# Yitran_IT900_Hutschiene_PIM7A_1_3.net
KiCad netlist of a schematic drawn in EAGLE
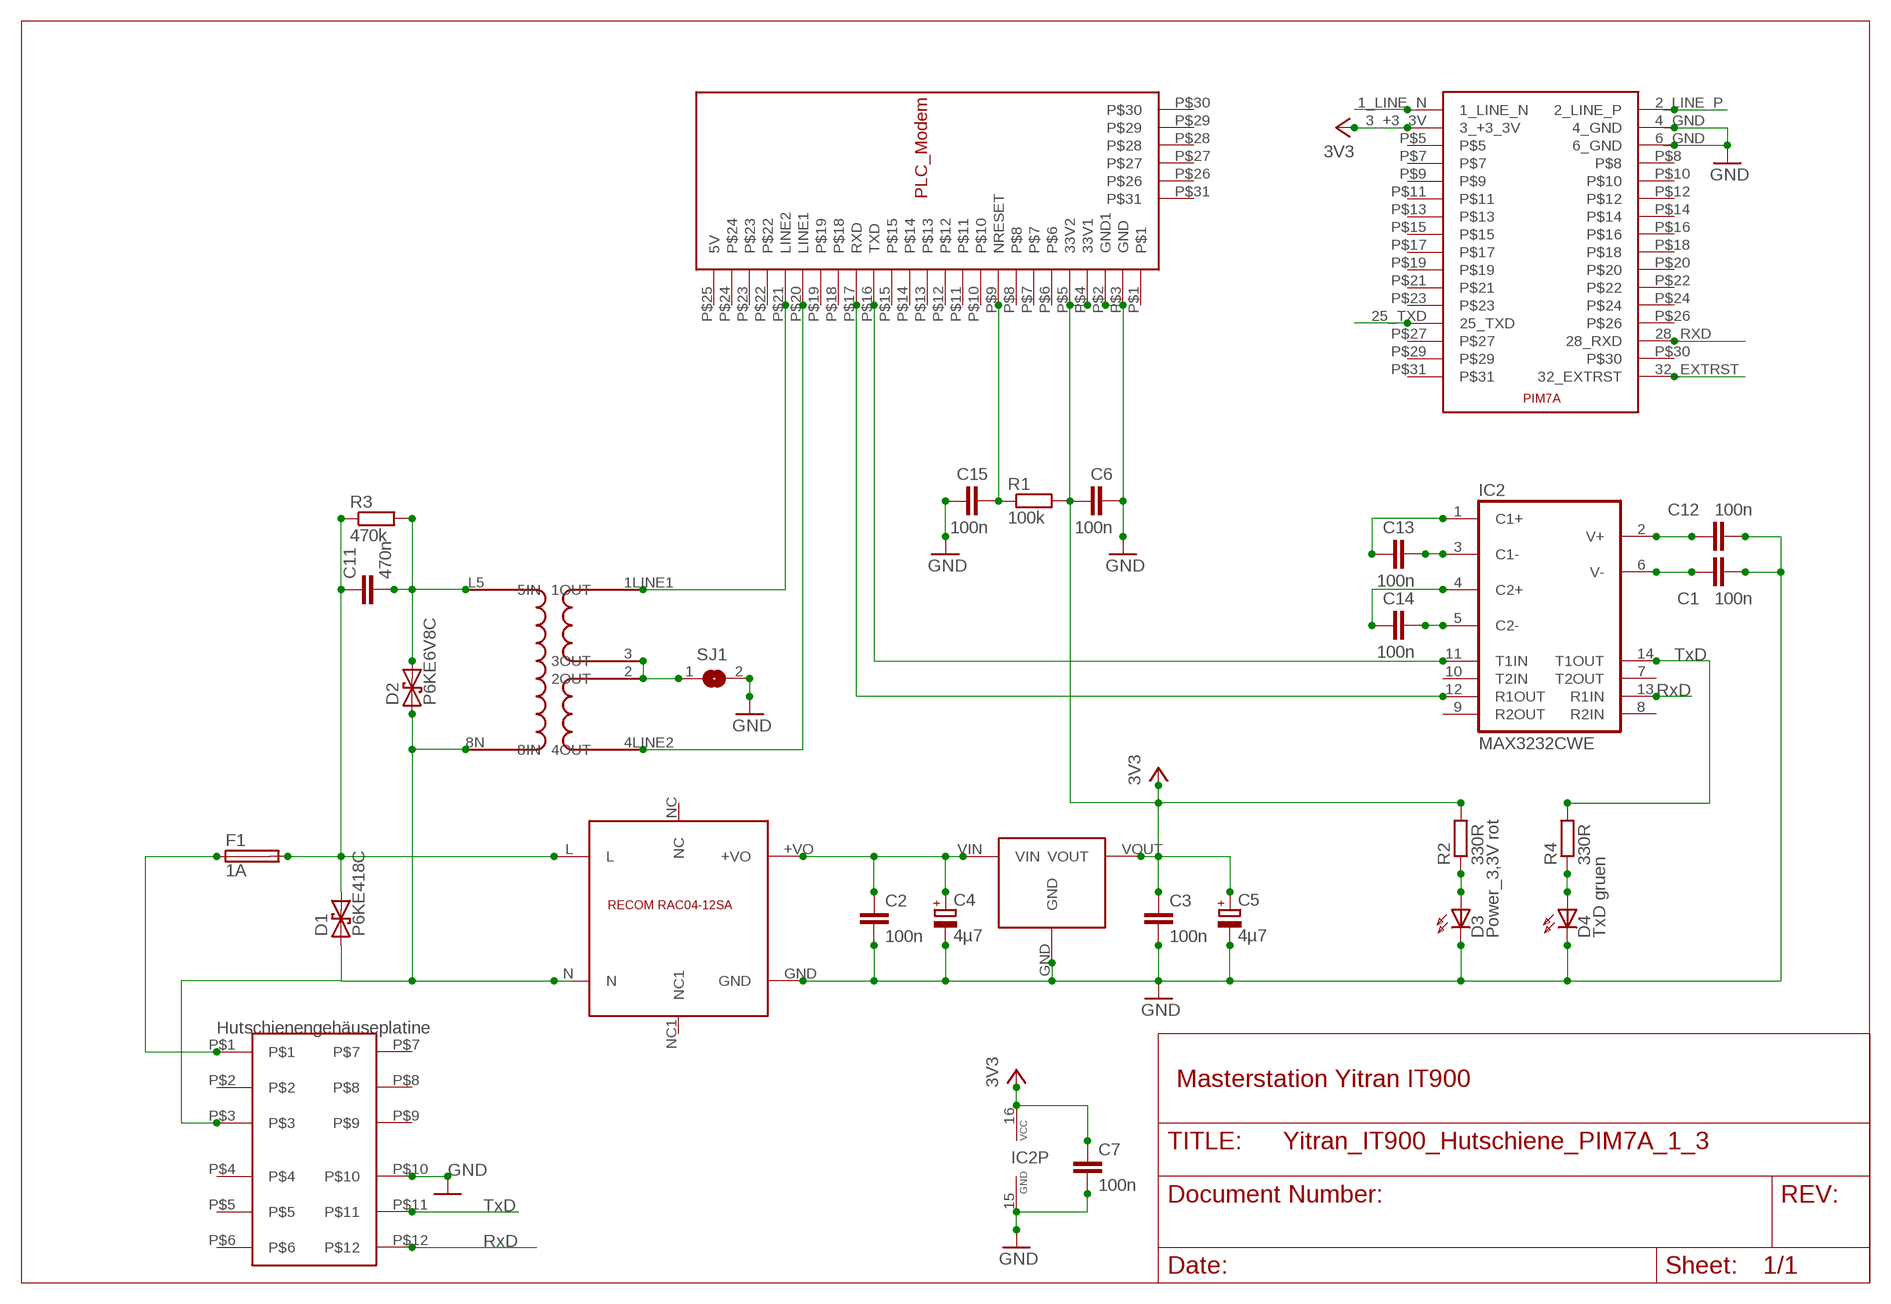
[diagram p0: schematic, sheet 1]

(export (version "E")
  (design (tool "Eeschema 10.0.6"))
  (components
    (comp (ref "C1")
      (value "100n")
      (footprint "eagle-import:C1206K")
      (libsource (lib "eagle-import") (part "C-EUC1206K"))
    )
    (comp (ref "C2")
      (value "100n")
      (footprint "eagle-import:C1206K")
      (libsource (lib "eagle-import") (part "C-EUC1206K"))
    )
    (comp (ref "C3")
      (value "100n")
      (footprint "eagle-import:C1206K")
      (libsource (lib "eagle-import") (part "C-EUC1206K"))
    )
    (comp (ref "C4")
      (value "4µ7")
      (footprint "eagle-import:E2,5-5")
      (libsource (lib "eagle-import") (part "CPOL-EUE2.5-5"))
    )
    (comp (ref "C5")
      (value "4µ7")
      (footprint "eagle-import:E2,5-5")
      (libsource (lib "eagle-import") (part "CPOL-EUE2.5-5"))
    )
    (comp (ref "C6")
      (value "100n")
      (footprint "eagle-import:C1206K")
      (libsource (lib "eagle-import") (part "C-EUC1206K"))
    )
    (comp (ref "C7")
      (value "100n")
      (footprint "eagle-import:C1206K")
      (libsource (lib "eagle-import") (part "C-EUC1206K"))
    )
    (comp (ref "C11")
      (value "470n")
      (footprint "eagle-import:C150-091X182")
      (libsource (lib "eagle-import") (part "C-EU150-091X182"))
    )
    (comp (ref "C12")
      (value "100n")
      (footprint "eagle-import:C1206K")
      (libsource (lib "eagle-import") (part "C-EUC1206K"))
    )
    (comp (ref "C13")
      (value "100n")
      (footprint "eagle-import:C1206K")
      (libsource (lib "eagle-import") (part "C-EUC1206K"))
    )
    (comp (ref "C14")
      (value "100n")
      (footprint "eagle-import:C1206K")
      (libsource (lib "eagle-import") (part "C-EUC1206K"))
    )
    (comp (ref "C15")
      (value "100n")
      (footprint "eagle-import:C1206K")
      (libsource (lib "eagle-import") (part "C-EUC1206K"))
    )
    (comp (ref "D1")
      (value "P6KE418C")
      (footprint "eagle-import:CB417-15")
      (libsource (lib "eagle-import") (part "P6KEXXC"))
    )
    (comp (ref "D2")
      (value "P6KE6V8C")
      (footprint "eagle-import:CB417-15")
      (libsource (lib "eagle-import") (part "P6KEXXC"))
    )
    (comp (ref "D3")
      (value "Power_3,3V rot")
      (footprint "eagle-import:HLMP6")
      (fields (field (name "MF") "AGILENT TECHNOLOGIES") (field (name "MPN") "HLMP-6500"))
      (libsource (lib "eagle-import") (part "HLMP6"))
    )
    (comp (ref "D4")
      (value "TxD gruen")
      (footprint "eagle-import:HLMP6")
      (fields (field (name "MF") "AGILENT TECHNOLOGIES") (field (name "MPN") "HLMP-6500"))
      (libsource (lib "eagle-import") (part "HLMP6"))
    )
    (comp (ref "F1")
      (value "1A")
      (footprint "eagle-import:TR5")
      (libsource (lib "eagle-import") (part "TR5"))
    )
    (comp (ref "IC2")
      (value "MAX3232CWE")
      (footprint "eagle-import:SO16L")
      (fields (field (name "MF") "MAXIM") (field (name "MPN") "MAX3232CWE+"))
      (libsource (lib "eagle-import") (part "MAX3232WEC"))
    )
    (comp (ref "R1")
      (value "100k")
      (footprint "eagle-import:M1406")
      (libsource (lib "eagle-import") (part "R-EU_M1406"))
    )
    (comp (ref "R2")
      (value "330R")
      (footprint "eagle-import:R1206")
      (libsource (lib "eagle-import") (part "R-EU_R1206"))
    )
    (comp (ref "R3")
      (value "470k")
      (footprint "eagle-import:0309_10")
      (libsource (lib "eagle-import") (part "R-EU_0309/10"))
    )
    (comp (ref "R4")
      (value "330R")
      (footprint "eagle-import:R1206")
      (libsource (lib "eagle-import") (part "R-EU_R1206"))
    )
    (comp (ref "SJ1")
      (value "SJW")
      (footprint "eagle-import:SJW")
      (libsource (lib "eagle-import") (part "SJW"))
    )
    (comp (ref "U$1")
      (value "RECOM_783_3")
      (footprint "eagle-import:RECOM785X")
      (libsource (lib "eagle-import") (part "RECOM_785_05"))
    )
    (comp (ref "U$2")
      (value "LDG-A-12")
      (footprint "eagle-import:LDG-A-12")
      (libsource (lib "eagle-import") (part "LDG-A-12"))
    )
    (comp (ref "U$3")
      (value "MODEMSTECKER")
      (footprint "eagle-import:MODEM_FUSS")
      (libsource (lib "eagle-import") (part "MODEMSTECKER"))
    )
    (comp (ref "U$4")
      (value "IT900PIM7A")
      (footprint "eagle-import:IT900PIM7A")
      (libsource (lib "eagle-import") (part "IT900PIM7A"))
    )
    (comp (ref "U$9")
      (value "RECOM_RAC04_12SA")
      (footprint "eagle-import:RAC04_12SA")
      (libsource (lib "eagle-import") (part "RECOM_RAC04_12SA"))
    )
    (comp (ref "U$10")
      (value "PLC_UEBERTRAGER_V2")
      (footprint "eagle-import:PLC-UEBERTRAGER_V2")
      (libsource (lib "eagle-import") (part "PLC_UEBERTRAGER_V2"))
    )
  )
  (nets
    (net (code "1") (name "/EXTRST") (class "Default")
      (node (ref "C15") (pin "2") (pinfunction "2_2") (pintype "passive"))
      (node (ref "R1") (pin "1") (pinfunction "1_1") (pintype "passive"))
      (node (ref "U$3") (pin "P$9") (pinfunction "NRESET_P$9") (pintype "bidirectional"))
      (node (ref "U$4") (pin "32_EXTRST") (pinfunction "32_EXTRST_32_EXTRST") (pintype "bidirectional"))
    )
    (net (code "2") (name "/LINE1") (class "Default")
      (node (ref "U$10") (pin "4LINE2") (pinfunction "4OUT_4LINE2") (pintype "output"))
      (node (ref "U$3") (pin "P$20") (pinfunction "LINE1_P$20") (pintype "bidirectional"))
      (node (ref "U$4") (pin "1_LINE_N") (pinfunction "1_LINE_N_1_LINE_N") (pintype "bidirectional"))
    )
    (net (code "3") (name "/LINE2") (class "Default")
      (node (ref "U$10") (pin "1LINE1") (pinfunction "1OUT_1LINE1") (pintype "output"))
      (node (ref "U$3") (pin "P$21") (pinfunction "LINE2_P$21") (pintype "bidirectional"))
      (node (ref "U$4") (pin "2_LINE_P") (pinfunction "2_LINE_P_2_LINE_P") (pintype "bidirectional"))
    )
    (net (code "4") (name "/RX") (class "Default")
      (node (ref "IC2") (pin "12") (pinfunction "R1OUT_12") (pintype "output"))
      (node (ref "U$3") (pin "P$17") (pinfunction "RXD_P$17") (pintype "bidirectional"))
      (node (ref "U$4") (pin "28_RXD") (pinfunction "28_RXD_28_RXD") (pintype "bidirectional"))
    )
    (net (code "5") (name "/RXD") (class "Default")
      (node (ref "IC2") (pin "13") (pinfunction "R1IN_13") (pintype "input"))
      (node (ref "U$2") (pin "P$12") (pinfunction "P$12_P$12") (pintype "bidirectional"))
    )
    (net (code "6") (name "/TX") (class "Default")
      (node (ref "IC2") (pin "11") (pinfunction "T1IN_11") (pintype "input"))
      (node (ref "U$3") (pin "P$16") (pinfunction "TXD_P$16") (pintype "bidirectional"))
      (node (ref "U$4") (pin "25_TXD") (pinfunction "25_TXD_25_TXD") (pintype "bidirectional"))
    )
    (net (code "7") (name "/TXD") (class "Default")
      (node (ref "IC2") (pin "14") (pinfunction "T1OUT_14") (pintype "output"))
      (node (ref "R4") (pin "2") (pinfunction "2_2") (pintype "passive"))
      (node (ref "U$2") (pin "P$11") (pinfunction "P$11_P$11") (pintype "bidirectional"))
    )
    (net (code "8") (name "3V3") (class "Default")
      (node (ref "C3") (pin "1") (pinfunction "1_1") (pintype "passive"))
      (node (ref "C5") (pin "+") (pinfunction "+_+") (pintype "passive"))
      (node (ref "C6") (pin "1") (pinfunction "1_1") (pintype "passive"))
      (node (ref "C7") (pin "1") (pinfunction "1_1") (pintype "passive"))
      (node (ref "IC2") (pin "16") (pinfunction "VCC_16") (pintype "power_in"))
      (node (ref "R1") (pin "2") (pinfunction "2_2") (pintype "passive"))
      (node (ref "R2") (pin "2") (pinfunction "2_2") (pintype "passive"))
      (node (ref "U$1") (pin "VOUT") (pinfunction "VOUT_VOUT") (pintype "bidirectional"))
      (node (ref "U$3") (pin "P$4") (pinfunction "33V1_P$4") (pintype "bidirectional"))
      (node (ref "U$3") (pin "P$5") (pinfunction "33V2_P$5") (pintype "bidirectional"))
      (node (ref "U$4") (pin "3_+3_3V") (pinfunction "3_+3_3V_3_+3_3V") (pintype "bidirectional"))
    )
    (net (code "9") (name "GND") (class "Default")
      (node (ref "C1") (pin "2") (pinfunction "2_2") (pintype "passive"))
      (node (ref "C12") (pin "2") (pinfunction "2_2") (pintype "passive"))
      (node (ref "C15") (pin "1") (pinfunction "1_1") (pintype "passive"))
      (node (ref "C2") (pin "2") (pinfunction "2_2") (pintype "passive"))
      (node (ref "C3") (pin "2") (pinfunction "2_2") (pintype "passive"))
      (node (ref "C4") (pin "-") (pinfunction "-_-") (pintype "passive"))
      (node (ref "C5") (pin "-") (pinfunction "-_-") (pintype "passive"))
      (node (ref "C6") (pin "2") (pinfunction "2_2") (pintype "passive"))
      (node (ref "C7") (pin "2") (pinfunction "2_2") (pintype "passive"))
      (node (ref "D3") (pin "K") (pinfunction "K_K") (pintype "passive"))
      (node (ref "D4") (pin "K") (pinfunction "K_K") (pintype "passive"))
      (node (ref "IC2") (pin "15") (pinfunction "GND_15") (pintype "power_in"))
      (node (ref "SJ1") (pin "2") (pinfunction "2_2") (pintype "passive"))
      (node (ref "U$1") (pin "GND") (pinfunction "GND_GND") (pintype "bidirectional"))
      (node (ref "U$2") (pin "P$10") (pinfunction "P$10_P$10") (pintype "bidirectional"))
      (node (ref "U$3") (pin "P$2") (pinfunction "GND1_P$2") (pintype "bidirectional"))
      (node (ref "U$3") (pin "P$3") (pinfunction "GND_P$3") (pintype "bidirectional"))
      (node (ref "U$4") (pin "4_GND") (pinfunction "4_GND_4_GND") (pintype "bidirectional"))
      (node (ref "U$4") (pin "6_GND") (pinfunction "6_GND_6_GND") (pintype "bidirectional"))
      (node (ref "U$9") (pin "GND") (pinfunction "GND_GND") (pintype "bidirectional"))
    )
    (net (code "10") (name "Net-(C2-Pad1)") (class "Default")
      (node (ref "C2") (pin "1") (pinfunction "1_1") (pintype "passive"))
      (node (ref "C4") (pin "+") (pinfunction "+_+") (pintype "passive"))
      (node (ref "U$1") (pin "VIN") (pinfunction "VIN_VIN") (pintype "bidirectional"))
      (node (ref "U$9") (pin "+VO") (pinfunction "+VO_+VO") (pintype "bidirectional"))
    )
    (net (code "11") (name "Net-(D1-1)") (class "Default")
      (node (ref "D1") (pin "A") (pinfunction "1_A") (pintype "passive"))
      (node (ref "D2") (pin "A") (pinfunction "1_A") (pintype "passive"))
      (node (ref "U$10") (pin "8N") (pinfunction "8IN_8N") (pintype "input"))
      (node (ref "U$2") (pin "P$3") (pinfunction "P$3_P$3") (pintype "bidirectional"))
      (node (ref "U$9") (pin "N") (pinfunction "N_N") (pintype "bidirectional"))
    )
    (net (code "12") (name "Net-(D1-2)") (class "Default")
      (node (ref "C11") (pin "1") (pinfunction "1_1") (pintype "passive"))
      (node (ref "D1") (pin "C") (pinfunction "2_C") (pintype "passive"))
      (node (ref "F1") (pin "2") (pinfunction "2_2") (pintype "passive"))
      (node (ref "R3") (pin "1") (pinfunction "1_1") (pintype "passive"))
      (node (ref "U$9") (pin "L") (pinfunction "L_L") (pintype "bidirectional"))
    )
    (net (code "13") (name "Net-(D2-2)") (class "Default")
      (node (ref "C11") (pin "2") (pinfunction "2_2") (pintype "passive"))
      (node (ref "D2") (pin "C") (pinfunction "2_C") (pintype "passive"))
      (node (ref "R3") (pin "2") (pinfunction "2_2") (pintype "passive"))
      (node (ref "U$10") (pin "L5") (pinfunction "5IN_L5") (pintype "input"))
    )
    (net (code "14") (name "Net-(D3-PadA)") (class "Default")
      (node (ref "D3") (pin "A") (pinfunction "A_A") (pintype "passive"))
      (node (ref "R2") (pin "1") (pinfunction "1_1") (pintype "passive"))
    )
    (net (code "15") (name "Net-(D4-PadA)") (class "Default")
      (node (ref "D4") (pin "A") (pinfunction "A_A") (pintype "passive"))
      (node (ref "R4") (pin "1") (pinfunction "1_1") (pintype "passive"))
    )
    (net (code "16") (name "Net-(F1-Pad1)") (class "Default")
      (node (ref "F1") (pin "1") (pinfunction "1_1") (pintype "passive"))
      (node (ref "U$2") (pin "P$1") (pinfunction "P$1_P$1") (pintype "bidirectional"))
    )
    (net (code "17") (name "Net-(IC2A-C1+)") (class "Default")
      (node (ref "C13") (pin "1") (pinfunction "1_1") (pintype "passive"))
      (node (ref "IC2") (pin "1") (pinfunction "C1+_1") (pintype "bidirectional"))
    )
    (net (code "18") (name "Net-(IC2A-C1-)") (class "Default")
      (node (ref "C13") (pin "2") (pinfunction "2_2") (pintype "passive"))
      (node (ref "IC2") (pin "3") (pinfunction "C1-_3") (pintype "bidirectional"))
    )
    (net (code "19") (name "Net-(IC2A-C2+)") (class "Default")
      (node (ref "C14") (pin "1") (pinfunction "1_1") (pintype "passive"))
      (node (ref "IC2") (pin "4") (pinfunction "C2+_4") (pintype "bidirectional"))
    )
    (net (code "20") (name "Net-(IC2A-C2-)") (class "Default")
      (node (ref "C14") (pin "2") (pinfunction "2_2") (pintype "passive"))
      (node (ref "IC2") (pin "5") (pinfunction "C2-_5") (pintype "bidirectional"))
    )
    (net (code "21") (name "Net-(IC2A-V+)") (class "Default")
      (node (ref "C12") (pin "1") (pinfunction "1_1") (pintype "passive"))
      (node (ref "IC2") (pin "2") (pinfunction "V+_2") (pintype "bidirectional"))
    )
    (net (code "22") (name "Net-(IC2A-V-)") (class "Default")
      (node (ref "C1") (pin "1") (pinfunction "1_1") (pintype "passive"))
      (node (ref "IC2") (pin "6") (pinfunction "V-_6") (pintype "bidirectional"))
    )
    (net (code "23") (name "Net-(U$10-2OUT)") (class "Default")
      (node (ref "SJ1") (pin "1") (pinfunction "1_1") (pintype "passive"))
      (node (ref "U$10") (pin "2") (pinfunction "2OUT_2") (pintype "output"))
      (node (ref "U$10") (pin "3") (pinfunction "3OUT_3") (pintype "output"))
    )
    (net (code "24") (name "unconnected-(IC2A-R2IN-Pad8)") (class "Default")
      (node (ref "IC2") (pin "8") (pinfunction "R2IN_8") (pintype "input"))
    )
    (net (code "25") (name "unconnected-(IC2A-R2OUT-Pad9)") (class "Default")
      (node (ref "IC2") (pin "9") (pinfunction "R2OUT_9") (pintype "output"))
    )
    (net (code "26") (name "unconnected-(IC2A-T2IN-Pad10)") (class "Default")
      (node (ref "IC2") (pin "10") (pinfunction "T2IN_10") (pintype "input"))
    )
    (net (code "27") (name "unconnected-(IC2A-T2OUT-Pad7)") (class "Default")
      (node (ref "IC2") (pin "7") (pinfunction "T2OUT_7") (pintype "output"))
    )
    (net (code "28") (name "unconnected-(U$2-PadP$2)") (class "Default")
      (node (ref "U$2") (pin "P$2") (pinfunction "P$2_P$2") (pintype "bidirectional"))
    )
    (net (code "29") (name "unconnected-(U$2-PadP$4)") (class "Default")
      (node (ref "U$2") (pin "P$4") (pinfunction "P$4_P$4") (pintype "bidirectional"))
    )
    (net (code "30") (name "unconnected-(U$2-PadP$5)") (class "Default")
      (node (ref "U$2") (pin "P$5") (pinfunction "P$5_P$5") (pintype "bidirectional"))
    )
    (net (code "31") (name "unconnected-(U$2-PadP$6)") (class "Default")
      (node (ref "U$2") (pin "P$6") (pinfunction "P$6_P$6") (pintype "bidirectional"))
    )
    (net (code "32") (name "unconnected-(U$2-PadP$7)") (class "Default")
      (node (ref "U$2") (pin "P$7") (pinfunction "P$7_P$7") (pintype "bidirectional"))
    )
    (net (code "33") (name "unconnected-(U$2-PadP$8)") (class "Default")
      (node (ref "U$2") (pin "P$8") (pinfunction "P$8_P$8") (pintype "bidirectional"))
    )
    (net (code "34") (name "unconnected-(U$2-PadP$9)") (class "Default")
      (node (ref "U$2") (pin "P$9") (pinfunction "P$9_P$9") (pintype "bidirectional"))
    )
    (net (code "35") (name "unconnected-(U$3-5V-PadP$25)") (class "Default")
      (node (ref "U$3") (pin "P$25") (pinfunction "5V_P$25") (pintype "bidirectional"))
    )
    (net (code "36") (name "unconnected-(U$3-PadP$1)") (class "Default")
      (node (ref "U$3") (pin "P$1") (pinfunction "P$1_P$1") (pintype "bidirectional"))
    )
    (net (code "37") (name "unconnected-(U$3-PadP$6)") (class "Default")
      (node (ref "U$3") (pin "P$6") (pinfunction "P$6_P$6") (pintype "bidirectional"))
    )
    (net (code "38") (name "unconnected-(U$3-PadP$7)") (class "Default")
      (node (ref "U$3") (pin "P$7") (pinfunction "P$7_P$7") (pintype "bidirectional"))
    )
    (net (code "39") (name "unconnected-(U$3-PadP$8)") (class "Default")
      (node (ref "U$3") (pin "P$8") (pinfunction "P$8_P$8") (pintype "bidirectional"))
    )
    (net (code "40") (name "unconnected-(U$3-PadP$10)") (class "Default")
      (node (ref "U$3") (pin "P$10") (pinfunction "P$10_P$10") (pintype "bidirectional"))
    )
    (net (code "41") (name "unconnected-(U$3-PadP$11)") (class "Default")
      (node (ref "U$3") (pin "P$11") (pinfunction "P$11_P$11") (pintype "bidirectional"))
    )
    (net (code "42") (name "unconnected-(U$3-PadP$12)") (class "Default")
      (node (ref "U$3") (pin "P$12") (pinfunction "P$12_P$12") (pintype "bidirectional"))
    )
    (net (code "43") (name "unconnected-(U$3-PadP$13)") (class "Default")
      (node (ref "U$3") (pin "P$13") (pinfunction "P$13_P$13") (pintype "bidirectional"))
    )
    (net (code "44") (name "unconnected-(U$3-PadP$14)") (class "Default")
      (node (ref "U$3") (pin "P$14") (pinfunction "P$14_P$14") (pintype "bidirectional"))
    )
    (net (code "45") (name "unconnected-(U$3-PadP$15)") (class "Default")
      (node (ref "U$3") (pin "P$15") (pinfunction "P$15_P$15") (pintype "bidirectional"))
    )
    (net (code "46") (name "unconnected-(U$3-PadP$18)") (class "Default")
      (node (ref "U$3") (pin "P$18") (pinfunction "P$18_P$18") (pintype "bidirectional"))
    )
    (net (code "47") (name "unconnected-(U$3-PadP$19)") (class "Default")
      (node (ref "U$3") (pin "P$19") (pinfunction "P$19_P$19") (pintype "bidirectional"))
    )
    (net (code "48") (name "unconnected-(U$3-PadP$22)") (class "Default")
      (node (ref "U$3") (pin "P$22") (pinfunction "P$22_P$22") (pintype "bidirectional"))
    )
    (net (code "49") (name "unconnected-(U$3-PadP$23)") (class "Default")
      (node (ref "U$3") (pin "P$23") (pinfunction "P$23_P$23") (pintype "bidirectional"))
    )
    (net (code "50") (name "unconnected-(U$3-PadP$24)") (class "Default")
      (node (ref "U$3") (pin "P$24") (pinfunction "P$24_P$24") (pintype "bidirectional"))
    )
    (net (code "51") (name "unconnected-(U$3-PadP$26)") (class "Default")
      (node (ref "U$3") (pin "P$26") (pinfunction "P$26_P$26") (pintype "bidirectional"))
    )
    (net (code "52") (name "unconnected-(U$3-PadP$27)") (class "Default")
      (node (ref "U$3") (pin "P$27") (pinfunction "P$27_P$27") (pintype "bidirectional"))
    )
    (net (code "53") (name "unconnected-(U$3-PadP$28)") (class "Default")
      (node (ref "U$3") (pin "P$28") (pinfunction "P$28_P$28") (pintype "bidirectional"))
    )
    (net (code "54") (name "unconnected-(U$3-PadP$29)") (class "Default")
      (node (ref "U$3") (pin "P$29") (pinfunction "P$29_P$29") (pintype "bidirectional"))
    )
    (net (code "55") (name "unconnected-(U$3-PadP$30)") (class "Default")
      (node (ref "U$3") (pin "P$30") (pinfunction "P$30_P$30") (pintype "bidirectional"))
    )
    (net (code "56") (name "unconnected-(U$3-PadP$31)") (class "Default")
      (node (ref "U$3") (pin "P$31") (pinfunction "P$31_P$31") (pintype "bidirectional"))
    )
    (net (code "57") (name "unconnected-(U$4-PadP$5)") (class "Default")
      (node (ref "U$4") (pin "P$5") (pinfunction "P$5_P$5") (pintype "bidirectional"))
    )
    (net (code "58") (name "unconnected-(U$4-PadP$7)") (class "Default")
      (node (ref "U$4") (pin "P$7") (pinfunction "P$7_P$7") (pintype "bidirectional"))
    )
    (net (code "59") (name "unconnected-(U$4-PadP$8)") (class "Default")
      (node (ref "U$4") (pin "P$8") (pinfunction "P$8_P$8") (pintype "bidirectional"))
    )
    (net (code "60") (name "unconnected-(U$4-PadP$9)") (class "Default")
      (node (ref "U$4") (pin "P$9") (pinfunction "P$9_P$9") (pintype "bidirectional"))
    )
    (net (code "61") (name "unconnected-(U$4-PadP$10)") (class "Default")
      (node (ref "U$4") (pin "P$10") (pinfunction "P$10_P$10") (pintype "bidirectional"))
    )
    (net (code "62") (name "unconnected-(U$4-PadP$11)") (class "Default")
      (node (ref "U$4") (pin "P$11") (pinfunction "P$11_P$11") (pintype "bidirectional"))
    )
    (net (code "63") (name "unconnected-(U$4-PadP$12)") (class "Default")
      (node (ref "U$4") (pin "P$12") (pinfunction "P$12_P$12") (pintype "bidirectional"))
    )
    (net (code "64") (name "unconnected-(U$4-PadP$13)") (class "Default")
      (node (ref "U$4") (pin "P$13") (pinfunction "P$13_P$13") (pintype "bidirectional"))
    )
    (net (code "65") (name "unconnected-(U$4-PadP$14)") (class "Default")
      (node (ref "U$4") (pin "P$14") (pinfunction "P$14_P$14") (pintype "bidirectional"))
    )
    (net (code "66") (name "unconnected-(U$4-PadP$15)") (class "Default")
      (node (ref "U$4") (pin "P$15") (pinfunction "P$15_P$15") (pintype "bidirectional"))
    )
    (net (code "67") (name "unconnected-(U$4-PadP$16)") (class "Default")
      (node (ref "U$4") (pin "P$16") (pinfunction "P$16_P$16") (pintype "bidirectional"))
    )
    (net (code "68") (name "unconnected-(U$4-PadP$17)") (class "Default")
      (node (ref "U$4") (pin "P$17") (pinfunction "P$17_P$17") (pintype "bidirectional"))
    )
    (net (code "69") (name "unconnected-(U$4-PadP$18)") (class "Default")
      (node (ref "U$4") (pin "P$18") (pinfunction "P$18_P$18") (pintype "bidirectional"))
    )
    (net (code "70") (name "unconnected-(U$4-PadP$19)") (class "Default")
      (node (ref "U$4") (pin "P$19") (pinfunction "P$19_P$19") (pintype "bidirectional"))
    )
    (net (code "71") (name "unconnected-(U$4-PadP$20)") (class "Default")
      (node (ref "U$4") (pin "P$20") (pinfunction "P$20_P$20") (pintype "bidirectional"))
    )
    (net (code "72") (name "unconnected-(U$4-PadP$21)") (class "Default")
      (node (ref "U$4") (pin "P$21") (pinfunction "P$21_P$21") (pintype "bidirectional"))
    )
    (net (code "73") (name "unconnected-(U$4-PadP$22)") (class "Default")
      (node (ref "U$4") (pin "P$22") (pinfunction "P$22_P$22") (pintype "bidirectional"))
    )
    (net (code "74") (name "unconnected-(U$4-PadP$23)") (class "Default")
      (node (ref "U$4") (pin "P$23") (pinfunction "P$23_P$23") (pintype "bidirectional"))
    )
    (net (code "75") (name "unconnected-(U$4-PadP$24)") (class "Default")
      (node (ref "U$4") (pin "P$24") (pinfunction "P$24_P$24") (pintype "bidirectional"))
    )
    (net (code "76") (name "unconnected-(U$4-PadP$26)") (class "Default")
      (node (ref "U$4") (pin "P$26") (pinfunction "P$26_P$26") (pintype "bidirectional"))
    )
    (net (code "77") (name "unconnected-(U$4-PadP$27)") (class "Default")
      (node (ref "U$4") (pin "P$27") (pinfunction "P$27_P$27") (pintype "bidirectional"))
    )
    (net (code "78") (name "unconnected-(U$4-PadP$29)") (class "Default")
      (node (ref "U$4") (pin "P$29") (pinfunction "P$29_P$29") (pintype "bidirectional"))
    )
    (net (code "79") (name "unconnected-(U$4-PadP$30)") (class "Default")
      (node (ref "U$4") (pin "P$30") (pinfunction "P$30_P$30") (pintype "bidirectional"))
    )
    (net (code "80") (name "unconnected-(U$4-PadP$31)") (class "Default")
      (node (ref "U$4") (pin "P$31") (pinfunction "P$31_P$31") (pintype "bidirectional"))
    )
    (net (code "81") (name "unconnected-(U$9-PadNC)") (class "Default")
      (node (ref "U$9") (pin "NC") (pinfunction "NC_NC") (pintype "bidirectional"))
    )
    (net (code "82") (name "unconnected-(U$9-PadNC1)") (class "Default")
      (node (ref "U$9") (pin "NC1") (pinfunction "NC1_NC1") (pintype "bidirectional"))
    )
  )
)
